# hvhc-opamp-v01.net
KiCad netlist of a schematic drawn in EAGLE
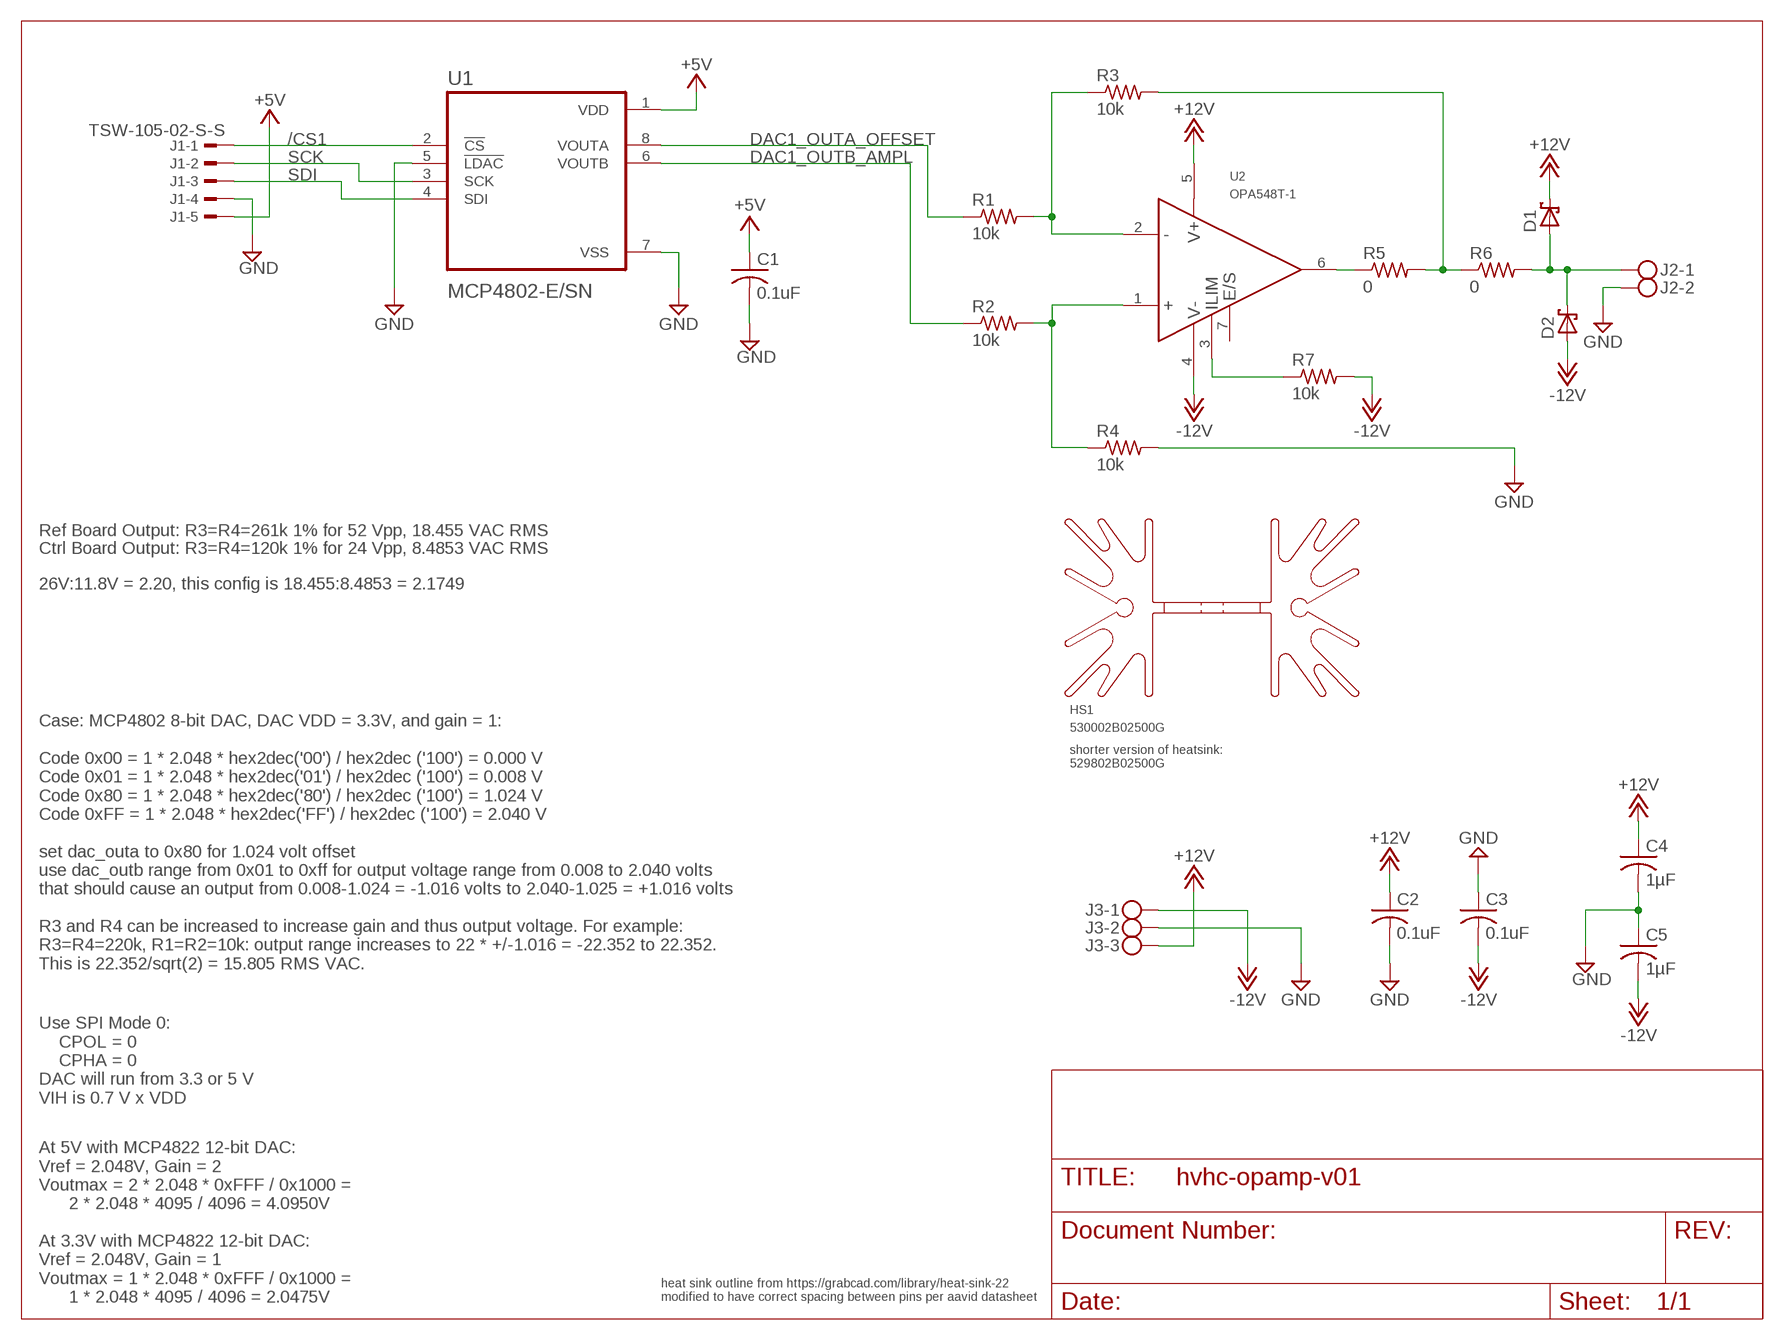
[diagram p0: schematic, sheet 1]

(export (version "E")
  (design (tool "Eeschema 10.0.6"))
  (components
    (comp (ref "C1")
      (value "0.1uF")
      (footprint "eagle-import:C0603K")
      (fields (field (name "MFR") "KEMET") (field (name "MFR_PART_NO") "C1206C104K5RACAUTO"))
      (libsource (lib "eagle-import") (part "C-USC0603K"))
    )
    (comp (ref "C2")
      (value "0.1uF")
      (footprint "eagle-import:C0603K")
      (fields (field (name "MFR") "KEMET") (field (name "MFR_PART_NO") "C1206C104K5RACAUTO"))
      (libsource (lib "eagle-import") (part "C-USC0603K"))
    )
    (comp (ref "C3")
      (value "0.1uF")
      (footprint "eagle-import:C0603K")
      (fields (field (name "MFR") "KEMET") (field (name "MFR_PART_NO") "C1206C104K5RACAUTO"))
      (libsource (lib "eagle-import") (part "C-USC0603K"))
    )
    (comp (ref "C4")
      (value "1µF")
      (footprint "eagle-import:C1206K")
      (libsource (lib "eagle-import") (part "C-USC1206K"))
    )
    (comp (ref "C5")
      (value "1µF")
      (footprint "eagle-import:C1206K")
      (libsource (lib "eagle-import") (part "C-USC1206K"))
    )
    (comp (ref "D1")
      (value "1N5819-B")
      (footprint "eagle-import:DO41-7.6")
      (libsource (lib "eagle-import") (part "1N5819-B"))
    )
    (comp (ref "D2")
      (value "1N5819-B")
      (footprint "eagle-import:DO41-7.6")
      (libsource (lib "eagle-import") (part "1N5819-B"))
    )
    (comp (ref "HS1")
      (value "530002B02500G")
      (footprint "eagle-import:530002B02500G")
      (libsource (lib "eagle-import") (part "530002B02500G"))
    )
    (comp (ref "J1")
      (value "TSW-105-02-S-S")
      (footprint "eagle-import:TSW-105-02-S-S")
      (libsource (lib "eagle-import") (part "TSW-105-02-S-S"))
    )
    (comp (ref "J2")
      (value "1711725")
      (footprint "eagle-import:1711725")
      (libsource (lib "eagle-import") (part "1711725"))
    )
    (comp (ref "J3")
      (value "1711738")
      (footprint "eagle-import:1711738")
      (libsource (lib "eagle-import") (part "1711738"))
    )
    (comp (ref "R1")
      (value "10k")
      (footprint "eagle-import:R1206")
      (libsource (lib "eagle-import") (part "R-US_R1206"))
    )
    (comp (ref "R2")
      (value "10k")
      (footprint "eagle-import:R1206")
      (libsource (lib "eagle-import") (part "R-US_R1206"))
    )
    (comp (ref "R3")
      (value "10k")
      (footprint "eagle-import:R1206")
      (libsource (lib "eagle-import") (part "R-US_R1206"))
    )
    (comp (ref "R4")
      (value "10k")
      (footprint "eagle-import:R1206")
      (libsource (lib "eagle-import") (part "R-US_R1206"))
    )
    (comp (ref "R5")
      (value "0")
      (footprint "eagle-import:R1206")
      (libsource (lib "eagle-import") (part "R-US_R1206"))
    )
    (comp (ref "R6")
      (value "0")
      (footprint "eagle-import:R1206")
      (libsource (lib "eagle-import") (part "R-US_R1206"))
    )
    (comp (ref "R7")
      (value "10k")
      (footprint "eagle-import:R1206")
      (libsource (lib "eagle-import") (part "R-US_R1206"))
    )
    (comp (ref "U1")
      (value "MCP4802-E/SN")
      (footprint "eagle-import:SOIC127P600X175-8N")
      (fields
        (field (name "DIGI-KEY_PART_NUMBER") "MCP4802-E/SN-ND")
        (field (name "MF") "Microchip Technology")
      )
      (libsource (lib "eagle-import") (part "MCP4802-E/SN"))
    )
    (comp (ref "U2")
      (value "OPA548T-1")
      (footprint "eagle-import:TO220-7-KC")
      (libsource (lib "eagle-import") (part "OPA548T-1"))
    )
  )
  (nets
    (net (code "1") (name "+5V") (class "Default")
      (node (ref "C1") (pin "1") (pinfunction "1_1") (pintype "passive"))
      (node (ref "J1") (pin "5") (pinfunction "1_5") (pintype "passive"))
      (node (ref "U1") (pin "1") (pinfunction "VDD_1") (pintype "power_in"))
    )
    (net (code "2") (name "+12V") (class "Default")
      (node (ref "C2") (pin "1") (pinfunction "1_1") (pintype "passive"))
      (node (ref "C4") (pin "1") (pinfunction "1_1") (pintype "passive"))
      (node (ref "D1") (pin "C") (pinfunction "C_C") (pintype "passive"))
      (node (ref "J3") (pin "3") (pinfunction "KL_3") (pintype "passive"))
      (node (ref "U2") (pin "5") (pinfunction "V+_5") (pintype "power_in"))
    )
    (net (code "3") (name "-12V") (class "Default")
      (node (ref "C3") (pin "2") (pinfunction "2_2") (pintype "passive"))
      (node (ref "C5") (pin "2") (pinfunction "2_2") (pintype "passive"))
      (node (ref "D2") (pin "A") (pinfunction "A_A") (pintype "passive"))
      (node (ref "J3") (pin "1") (pinfunction "KL_1") (pintype "passive"))
      (node (ref "R7") (pin "2") (pinfunction "2_2") (pintype "passive"))
      (node (ref "U2") (pin "4") (pinfunction "V-_4") (pintype "power_in"))
    )
    (net (code "4") (name "/DAC1_OUTA_OFFSET") (class "Default")
      (node (ref "R1") (pin "1") (pinfunction "1_1") (pintype "passive"))
      (node (ref "U1") (pin "8") (pinfunction "VOUTA_8") (pintype "output"))
    )
    (net (code "5") (name "/DAC1_OUTB_AMPL") (class "Default")
      (node (ref "R2") (pin "1") (pinfunction "1_1") (pintype "passive"))
      (node (ref "U1") (pin "6") (pinfunction "VOUTB_6") (pintype "output"))
    )
    (net (code "6") (name "/SCK") (class "Default")
      (node (ref "J1") (pin "2") (pinfunction "1_2") (pintype "passive"))
      (node (ref "U1") (pin "3") (pinfunction "SCK_3") (pintype "input"))
    )
    (net (code "7") (name "/SDI") (class "Default")
      (node (ref "J1") (pin "3") (pinfunction "1_3") (pintype "passive"))
      (node (ref "U1") (pin "4") (pinfunction "SDI_4") (pintype "input"))
    )
    (net (code "8") (name "/{slash}CS1") (class "Default")
      (node (ref "J1") (pin "1") (pinfunction "1_1") (pintype "passive"))
      (node (ref "U1") (pin "2") (pinfunction "~{CS}_2") (pintype "input"))
    )
    (net (code "9") (name "GND") (class "Default")
      (node (ref "C1") (pin "2") (pinfunction "2_2") (pintype "passive"))
      (node (ref "C2") (pin "2") (pinfunction "2_2") (pintype "passive"))
      (node (ref "C3") (pin "1") (pinfunction "1_1") (pintype "passive"))
      (node (ref "C4") (pin "2") (pinfunction "2_2") (pintype "passive"))
      (node (ref "C5") (pin "1") (pinfunction "1_1") (pintype "passive"))
      (node (ref "J1") (pin "4") (pinfunction "1_4") (pintype "passive"))
      (node (ref "J2") (pin "2") (pinfunction "KL_2") (pintype "passive"))
      (node (ref "J3") (pin "2") (pinfunction "KL_2") (pintype "passive"))
      (node (ref "R4") (pin "2") (pinfunction "2_2") (pintype "passive"))
      (node (ref "U1") (pin "5") (pinfunction "~{LDAC}_5") (pintype "input"))
      (node (ref "U1") (pin "7") (pinfunction "VSS_7") (pintype "power_in"))
    )
    (net (code "10") (name "Net-(J2A-KL)") (class "Default")
      (node (ref "D1") (pin "A") (pinfunction "A_A") (pintype "passive"))
      (node (ref "D2") (pin "C") (pinfunction "C_C") (pintype "passive"))
      (node (ref "J2") (pin "1") (pinfunction "KL_1") (pintype "passive"))
      (node (ref "R6") (pin "2") (pinfunction "2_2") (pintype "passive"))
    )
    (net (code "11") (name "Net-(R3-Pad2)") (class "Default")
      (node (ref "R3") (pin "2") (pinfunction "2_2") (pintype "passive"))
      (node (ref "R5") (pin "2") (pinfunction "2_2") (pintype "passive"))
      (node (ref "R6") (pin "1") (pinfunction "1_1") (pintype "passive"))
    )
    (net (code "12") (name "Net-(U2-ILIM)") (class "Default")
      (node (ref "R7") (pin "1") (pinfunction "1_1") (pintype "passive"))
      (node (ref "U2") (pin "3") (pinfunction "ILIM_3") (pintype "passive"))
    )
    (net (code "13") (name "Net-(U2-VIN+)") (class "Default")
      (node (ref "R2") (pin "2") (pinfunction "2_2") (pintype "passive"))
      (node (ref "R4") (pin "1") (pinfunction "1_1") (pintype "passive"))
      (node (ref "U2") (pin "1") (pinfunction "VIN+_1") (pintype "input"))
    )
    (net (code "14") (name "Net-(U2-VIN-)") (class "Default")
      (node (ref "R1") (pin "2") (pinfunction "2_2") (pintype "passive"))
      (node (ref "R3") (pin "1") (pinfunction "1_1") (pintype "passive"))
      (node (ref "U2") (pin "2") (pinfunction "VIN-_2") (pintype "input"))
    )
    (net (code "15") (name "Net-(U2-VO)") (class "Default")
      (node (ref "R5") (pin "1") (pinfunction "1_1") (pintype "passive"))
      (node (ref "U2") (pin "6") (pinfunction "VO_6") (pintype "output"))
    )
    (net (code "16") (name "unconnected-(U2-E{slash}S-Pad7)") (class "Default")
      (node (ref "U2") (pin "7") (pinfunction "E/S_7") (pintype "passive"))
    )
  )
)
